# BTVN3.net
KiCad netlist of a schematic drawn in Altium Designer
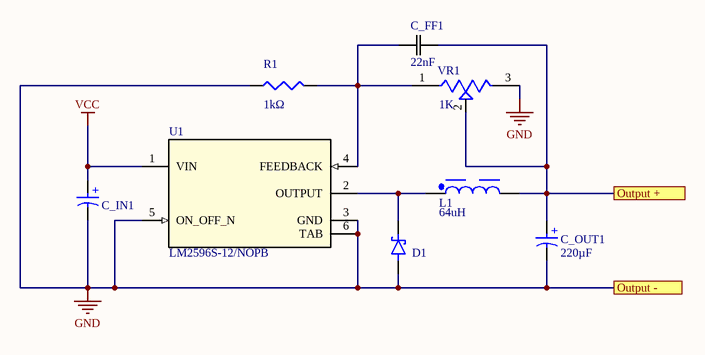
[diagram p0: BTVN3.SchDoc]

(export (version "E")
  (design (tool "Eeschema 10.0.6"))
  (components
    (comp (ref "C_FF1")
      (value "22nF")
      (footprint "CAPC340180_88N_KEM _1206")
      (description "No Description Available")
      (fields
        (field (name "MANUFACTURER_PART_NUMBER") "C1206C104K5RACTU")
        (field (name "COPYRIGHT") "Copyright (C) 2023 Ultra Librarian. All rights reserved.")
      )
      (libsource (lib "Integrated_Library_PPP") (part "Capacitor_SMD"))
    )
    (comp (ref "C_IN1")
      (value "470µF")
      (footprint "WCAP-AS5H_D6.3H7.7")
      (description "WCAP-AS5H Aluminum Electrolytic Capacitor, V-Chip, D10 x H10.5mm, 330µF, 50V")
      (fields
        (field (name "MANUFACTURER PART NUMBER") "865230657014")
        (field (name "MANUFACTURER") "Wurth Elektronik")
      )
      (libsource (lib "Integrated_Library_PPP") (part "Capacitor_Alumanium_SMD"))
    )
    (comp (ref "C_OUT1")
      (value "220µF")
      (footprint "WCAP-AS5H_D6.3H7.7")
      (description "WCAP-AS5H Aluminum Electrolytic Capacitor, V-Chip, D10 x H10.5mm, 330µF, 50V")
      (fields
        (field (name "MANUFACTURER PART NUMBER") "865230657014")
        (field (name "MANUFACTURER") "Wurth Elektronik")
      )
      (libsource (lib "Integrated_Library_PPP") (part "Capacitor_Alumanium_SMD"))
    )
    (comp (ref "D1")
      (value "Diode Schottky")
      (footprint "SODFL4725X110N")
      (description "Diode Schottky ?V ?A Surface Mount SMC")
      (fields (field (name "MP") "MBRS320T3G") (field (name "MF") "ON Semiconductor"))
      (libsource (lib "Integrated_Library_PPP") (part "Diode Schottky"))
    )
    (comp (ref "L1")
      (value "64uH")
      (footprint "WE-PD_1210")
      (description "WE-PD SMT Power Inductor, size ?, ?uH, ?A, ?Ohm")
      (fields
        (field (name "MANUFACTURER PART NUMBER") "7447709152")
        (field (name "MANUFACTURER") "Wurth Elektronik")
      )
      (libsource (lib "Integrated_Library_PPP") (part "Inductor_SMD"))
    )
    (comp (ref "R1")
      (value "1kΩ")
      (footprint "WRIS-PSMB_0603_L1.6W0.8H0.3")
      (description "WRIS-PSMC Metal Plate Resistor, SMT, size 2512, 2W, 5mΩ, +/-1%")
      (fields
        (field (name "MANUFACTURER PART NUMBER") "580070763005")
        (field (name "MANUFACTURER") "Wurth Elektronik")
      )
      (libsource (lib "Integrated_Library_PPP") (part "Resistor_SMD"))
    )
    (comp (ref "U1")
      (value "LM2596S-12/NOPB")
      (footprint "KTT0005B")
      (description "No Description Available")
      (fields
        (field (name "PARTNUMBER") "LM2596SX-ADJ/NOPB")
        (field (name "ALTERNATE_PARTNUMBER") "LM2596S-ADJ/NOPB")
        (field (name "COPYRIGHT") "Copyright (C) 2023 Ultra Librarian. All rights reserved.")
      )
      (libsource (lib "Integrated_Library_PPP") (part "LM2596S-12/NOPB"))
    )
    (comp (ref "VR1")
      (value "1K")
      (footprint "TRIM_3296W")
      (fields (field (name "MF") "Bourns") (field (name "MP") "3006P-1-202"))
      (libsource (lib "Integrated_Library_PPP") (part "Variable_Resistor"))
    )
  )
  (nets
    (net (code "1") (name "/Output +") (class "Default")
      (node (ref "C_FF1") (pin "2") (pinfunction "2_2") (pintype "passive"))
      (node (ref "C_OUT1") (pin "1") (pinfunction "P_1") (pintype "passive"))
      (node (ref "L1") (pin "2") (pinfunction "2_2") (pintype "passive"))
      (node (ref "VR1") (pin "2") (pinfunction "WIPER_2") (pintype "passive"))
    )
    (net (code "2") (name "GND") (class "Default")
      (node (ref "C_IN1") (pin "2") (pinfunction "N_2") (pintype "passive"))
      (node (ref "C_OUT1") (pin "2") (pinfunction "N_2") (pintype "passive"))
      (node (ref "D1") (pin "A") (pinfunction "A_A") (pintype "passive"))
      (node (ref "R1") (pin "1") (pinfunction "1_1") (pintype "passive"))
      (node (ref "U1") (pin "3") (pinfunction "GND_3") (pintype "power_in"))
      (node (ref "U1") (pin "5") (pinfunction "ON_OFF_N_5") (pintype "input"))
      (node (ref "U1") (pin "6") (pinfunction "TAB_6") (pintype "power_in"))
      (node (ref "VR1") (pin "3") (pinfunction "CW_3") (pintype "passive"))
    )
    (net (code "3") (name "Net-(D1-K)") (class "Default")
      (node (ref "D1") (pin "C") (pinfunction "K_C") (pintype "passive"))
      (node (ref "L1") (pin "1") (pinfunction "1_1") (pintype "passive"))
      (node (ref "U1") (pin "2") (pinfunction "OUTPUT_2") (pintype "power_in"))
    )
    (net (code "4") (name "Net-(U1-FEEDBACK)") (class "Default")
      (node (ref "C_FF1") (pin "1") (pinfunction "1_1") (pintype "passive"))
      (node (ref "R1") (pin "2") (pinfunction "2_2") (pintype "passive"))
      (node (ref "U1") (pin "4") (pinfunction "FEEDBACK_4") (pintype "input"))
      (node (ref "VR1") (pin "1") (pinfunction "CCW_1") (pintype "passive"))
    )
    (net (code "5") (name "VCC") (class "Default")
      (node (ref "C_IN1") (pin "1") (pinfunction "P_1") (pintype "passive"))
      (node (ref "U1") (pin "1") (pinfunction "VIN_1") (pintype "power_in"))
    )
  )
)
